# schMotores.net
KiCad netlist of a schematic drawn in Altium Designer
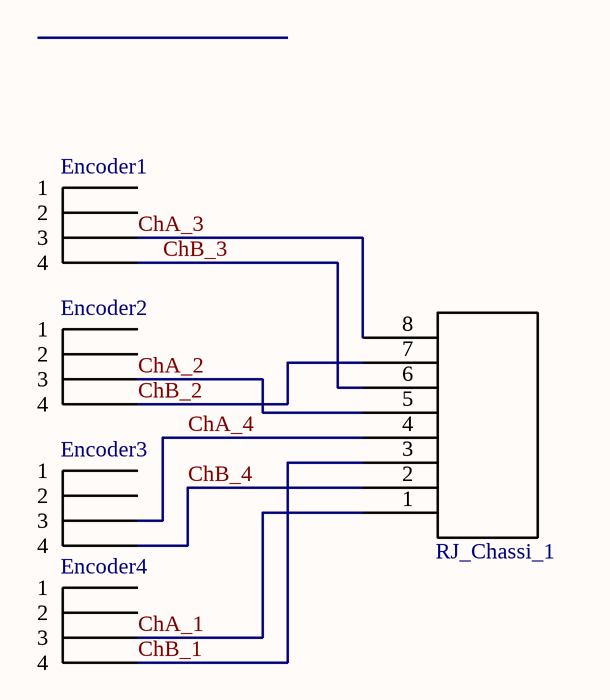
[diagram p0: schMotores.SchDoc]

(export (version "E")
  (design (tool "Eeschema 10.0.6"))
  (components
    (comp (ref "Encoder1")
      (value "KK4")
      (footprint "4-vias")
      (libsource (lib "Componentes_Open") (part "KK4Vias"))
    )
    (comp (ref "Encoder2")
      (value "KK4")
      (footprint "4-vias")
      (libsource (lib "Componentes_Open") (part "KK4Vias"))
    )
    (comp (ref "Encoder3")
      (value "KK4")
      (footprint "4-vias")
      (libsource (lib "Componentes_Open") (part "KK4Vias"))
    )
    (comp (ref "Encoder4")
      (value "KK4")
      (footprint "4-vias")
      (libsource (lib "Componentes_Open") (part "KK4Vias"))
    )
    (comp (ref "RJ_Chassi_1")
      (value "RJ45")
      (footprint "RJ45_90")
      (libsource (lib "Componentes_Open") (part "RJ45_90"))
    )
  )
  (nets
    (net (code "1") (name "/ChA_1") (class "Default")
      (node (ref "Encoder4") (pin "3") (pinfunction "3_3") (pintype "passive"))
      (node (ref "RJ_Chassi_1") (pin "1") (pinfunction "9_1") (pintype "passive"))
    )
    (net (code "2") (name "/ChA_2") (class "Default")
      (node (ref "Encoder2") (pin "3") (pinfunction "3_3") (pintype "passive"))
      (node (ref "RJ_Chassi_1") (pin "5") (pinfunction "5_5") (pintype "passive"))
    )
    (net (code "3") (name "/ChA_3") (class "Default")
      (node (ref "Encoder1") (pin "3") (pinfunction "3_3") (pintype "passive"))
      (node (ref "RJ_Chassi_1") (pin "8") (pinfunction "8_8") (pintype "passive"))
    )
    (net (code "4") (name "/ChA_4") (class "Default")
      (node (ref "Encoder3") (pin "3") (pinfunction "3_3") (pintype "passive"))
      (node (ref "RJ_Chassi_1") (pin "4") (pinfunction "4_4") (pintype "passive"))
    )
    (net (code "5") (name "/ChB_1") (class "Default")
      (node (ref "Encoder4") (pin "4") (pinfunction "4_4") (pintype "passive"))
      (node (ref "RJ_Chassi_1") (pin "3") (pinfunction "3_3") (pintype "passive"))
    )
    (net (code "6") (name "/ChB_2") (class "Default")
      (node (ref "Encoder2") (pin "4") (pinfunction "4_4") (pintype "passive"))
      (node (ref "RJ_Chassi_1") (pin "7") (pinfunction "7_7") (pintype "passive"))
    )
    (net (code "7") (name "/ChB_3") (class "Default")
      (node (ref "Encoder1") (pin "4") (pinfunction "4_4") (pintype "passive"))
      (node (ref "RJ_Chassi_1") (pin "6") (pinfunction "6_6") (pintype "passive"))
    )
    (net (code "8") (name "/ChB_4") (class "Default")
      (node (ref "Encoder3") (pin "4") (pinfunction "4_4") (pintype "passive"))
      (node (ref "RJ_Chassi_1") (pin "2") (pinfunction "2_2") (pintype "passive"))
    )
    (net (code "9") (name "unconnected-(Encoder1-Pad1)") (class "Default")
      (node (ref "Encoder1") (pin "1") (pinfunction "1_1") (pintype "passive"))
    )
    (net (code "10") (name "unconnected-(Encoder1-Pad2)") (class "Default")
      (node (ref "Encoder1") (pin "2") (pinfunction "2_2") (pintype "passive"))
    )
    (net (code "11") (name "unconnected-(Encoder2-Pad1)") (class "Default")
      (node (ref "Encoder2") (pin "1") (pinfunction "1_1") (pintype "passive"))
    )
    (net (code "12") (name "unconnected-(Encoder2-Pad2)") (class "Default")
      (node (ref "Encoder2") (pin "2") (pinfunction "2_2") (pintype "passive"))
    )
    (net (code "13") (name "unconnected-(Encoder3-Pad1)") (class "Default")
      (node (ref "Encoder3") (pin "1") (pinfunction "1_1") (pintype "passive"))
    )
    (net (code "14") (name "unconnected-(Encoder3-Pad2)") (class "Default")
      (node (ref "Encoder3") (pin "2") (pinfunction "2_2") (pintype "passive"))
    )
    (net (code "15") (name "unconnected-(Encoder4-Pad1)") (class "Default")
      (node (ref "Encoder4") (pin "1") (pinfunction "1_1") (pintype "passive"))
    )
    (net (code "16") (name "unconnected-(Encoder4-Pad2)") (class "Default")
      (node (ref "Encoder4") (pin "2") (pinfunction "2_2") (pintype "passive"))
    )
  )
)
